# dv_power_chanel.net
KiCad netlist of a schematic drawn in Altium Designer
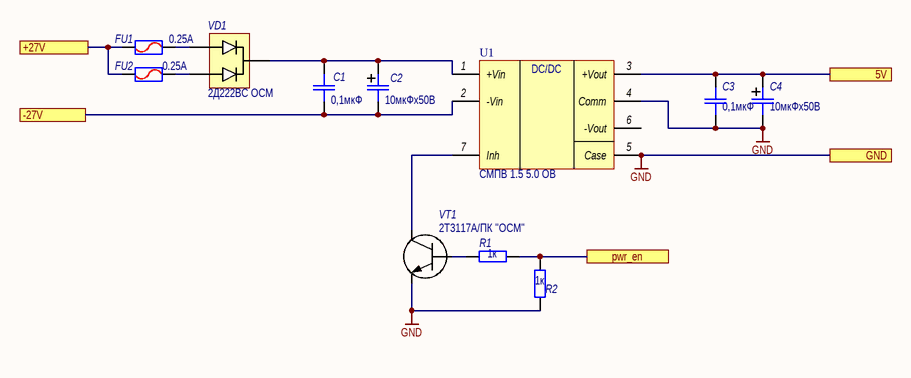
[diagram p0: dv_power_chanel.SchDoc]

(export (version "E")
  (design (tool "Eeschema 10.0.6"))
  (components
    (comp (ref "C1")
      (value "0,1мкФ")
      (footprint "SMD_C0805")
      (description "Capacitor")
      (fields (field (name "Comment") "K10-79"))
      (libsource (lib "Passive") (part "Capacitor"))
    )
    (comp (ref "C2")
      (value "10мкФх50В")
      (footprint "SMD_size_B")
      (description "Polarized capacitor")
      (fields (field (name "Comment") "OS K53-68"))
      (libsource (lib "Passive") (part "Capacitor_pol"))
    )
    (comp (ref "C3")
      (value "0,1мкФ")
      (footprint "SMD_C0805")
      (description "Capacitor")
      (fields (field (name "Comment") "K10-79"))
      (libsource (lib "Passive") (part "Capacitor"))
    )
    (comp (ref "C4")
      (value "10мкФх50В")
      (footprint "SMD_size_B")
      (description "Polarized capacitor")
      (fields (field (name "Comment") "OS K53-68"))
      (libsource (lib "Passive") (part "Capacitor_pol"))
    )
    (comp (ref "FU1")
      (value "0.25A")
      (footprint "VP1-2")
      (description "Предохранитель плавкий")
      (fields (field (name "Comment") "VP1-2"))
      (libsource (lib "Fuse") (part "VP1-2"))
    )
    (comp (ref "FU2")
      (value "0.25A")
      (footprint "VP1-2")
      (description "Предохранитель плавкий")
      (fields (field (name "Comment") "VP1-2"))
      (libsource (lib "Fuse") (part "VP1-2"))
    )
    (comp (ref "R1")
      (value "1к")
      (footprint "SMD_0805")
      (description "Resistor")
      (fields (field (name "Comment") "OSM R1-12"))
      (libsource (lib "") (part "Resistor_1"))
    )
    (comp (ref "R2")
      (value "1к")
      (footprint "SMD_0805")
      (description "Resistor")
      (fields (field (name "Comment") "OSM R1-12"))
      (libsource (lib "Passive") (part "Resistor"))
    )
    (comp (ref "U1")
      (value "SMPV 1.5 5.0 OV")
      (footprint "SLH28xx")
      (description "DC-DC")
      (fields (field (name "НАИМЕНОВАНИЕ") "СМПВ 1.5 5.0 ОВ"))
      (libsource (lib "DC_DC") (part "SLH28xx"))
    )
    (comp (ref "VD1")
      (value "2D222VS \"OSM\"")
      (footprint "4116.4-3_offcut")
      (description "Сдвоенный диод")
      (fields (field (name "НАИМЕНОВАНИЕ") "2Д222ВС ОСМ"))
      (libsource (lib "Diod") (part "2D222"))
    )
    (comp (ref "VT1")
      (value "2T3117A")
      (footprint "TO-18")
      (description "Кремниевый биполярный\r\nэпитаксиально-планарный\r\nn-p-n транзистор")
      (fields (field (name "НАИМЕНОВАНИЕ") "2Т3117А/ПК \"ОСМ\""))
      (libsource (lib "Transistor") (part "2T3117A"))
    )
  )
  (nets
    (net (code "1") (name "/+27V") (class "Default")
      (node (ref "FU1") (pin "1") (pinfunction "1_1") (pintype "passive"))
      (node (ref "FU2") (pin "1") (pinfunction "1_1") (pintype "passive"))
    )
    (net (code "2") (name "/-27V") (class "Default")
      (node (ref "C1") (pin "1") (pinfunction "1_1") (pintype "passive"))
      (node (ref "C2") (pin "2") (pinfunction "2_2") (pintype "passive"))
      (node (ref "U1") (pin "2") (pinfunction "-Vin_2") (pintype "open_collector"))
    )
    (net (code "3") (name "/5V") (class "Default")
      (node (ref "C3") (pin "2") (pinfunction "2_2") (pintype "passive"))
      (node (ref "C4") (pin "1") (pinfunction "1_1") (pintype "passive"))
      (node (ref "U1") (pin "3") (pinfunction "+Vout_3") (pintype "open_collector"))
    )
    (net (code "4") (name "/pwr_en") (class "Default")
      (node (ref "R1") (pin "2") (pinfunction "2_2") (pintype "passive"))
      (node (ref "R2") (pin "2") (pinfunction "2_2") (pintype "passive"))
    )
    (net (code "5") (name "GND") (class "Default")
      (node (ref "C3") (pin "1") (pinfunction "1_1") (pintype "passive"))
      (node (ref "C4") (pin "2") (pinfunction "2_2") (pintype "passive"))
      (node (ref "R2") (pin "1") (pinfunction "1_1") (pintype "passive"))
      (node (ref "U1") (pin "4") (pinfunction "Comm_4") (pintype "open_collector"))
      (node (ref "U1") (pin "5") (pinfunction "Case_5") (pintype "passive"))
      (node (ref "VT1") (pin "1") (pinfunction "EMITTER_1") (pintype "passive"))
    )
    (net (code "6") (name "Net-(FU1-Pad2)") (class "Default")
      (node (ref "FU1") (pin "2") (pinfunction "2_2") (pintype "passive"))
      (node (ref "VD1") (pin "11") (pintype "passive"))
    )
    (net (code "7") (name "Net-(FU2-Pad2)") (class "Default")
      (node (ref "FU2") (pin "2") (pinfunction "2_2") (pintype "passive"))
      (node (ref "VD1") (pin "17") (pintype "passive"))
    )
    (net (code "8") (name "Net-(U1-+Vin)") (class "Default")
      (node (ref "C1") (pin "2") (pinfunction "2_2") (pintype "passive"))
      (node (ref "C2") (pin "1") (pinfunction "1_1") (pintype "passive"))
      (node (ref "U1") (pin "1") (pinfunction "+Vin_1") (pintype "open_collector"))
      (node (ref "VD1") (pin "8") (pintype "passive"))
    )
    (net (code "9") (name "Net-(U1-Inh)") (class "Default")
      (node (ref "U1") (pin "7") (pinfunction "Inh_7") (pintype "open_collector"))
      (node (ref "VT1") (pin "3") (pinfunction "COLLECTOR_3") (pintype "passive"))
    )
    (net (code "10") (name "Net-(VT1-BASE)") (class "Default")
      (node (ref "R1") (pin "1") (pinfunction "1_1") (pintype "passive"))
      (node (ref "VT1") (pin "2") (pinfunction "BASE_2") (pintype "passive"))
    )
    (net (code "11") (name "unconnected-(U1--Vout-Pad6)") (class "Default")
      (node (ref "U1") (pin "6") (pinfunction "-Vout_6") (pintype "open_collector"))
    )
  )
)
